# Sheet2.net
KiCad netlist of a schematic drawn in Altium Designer
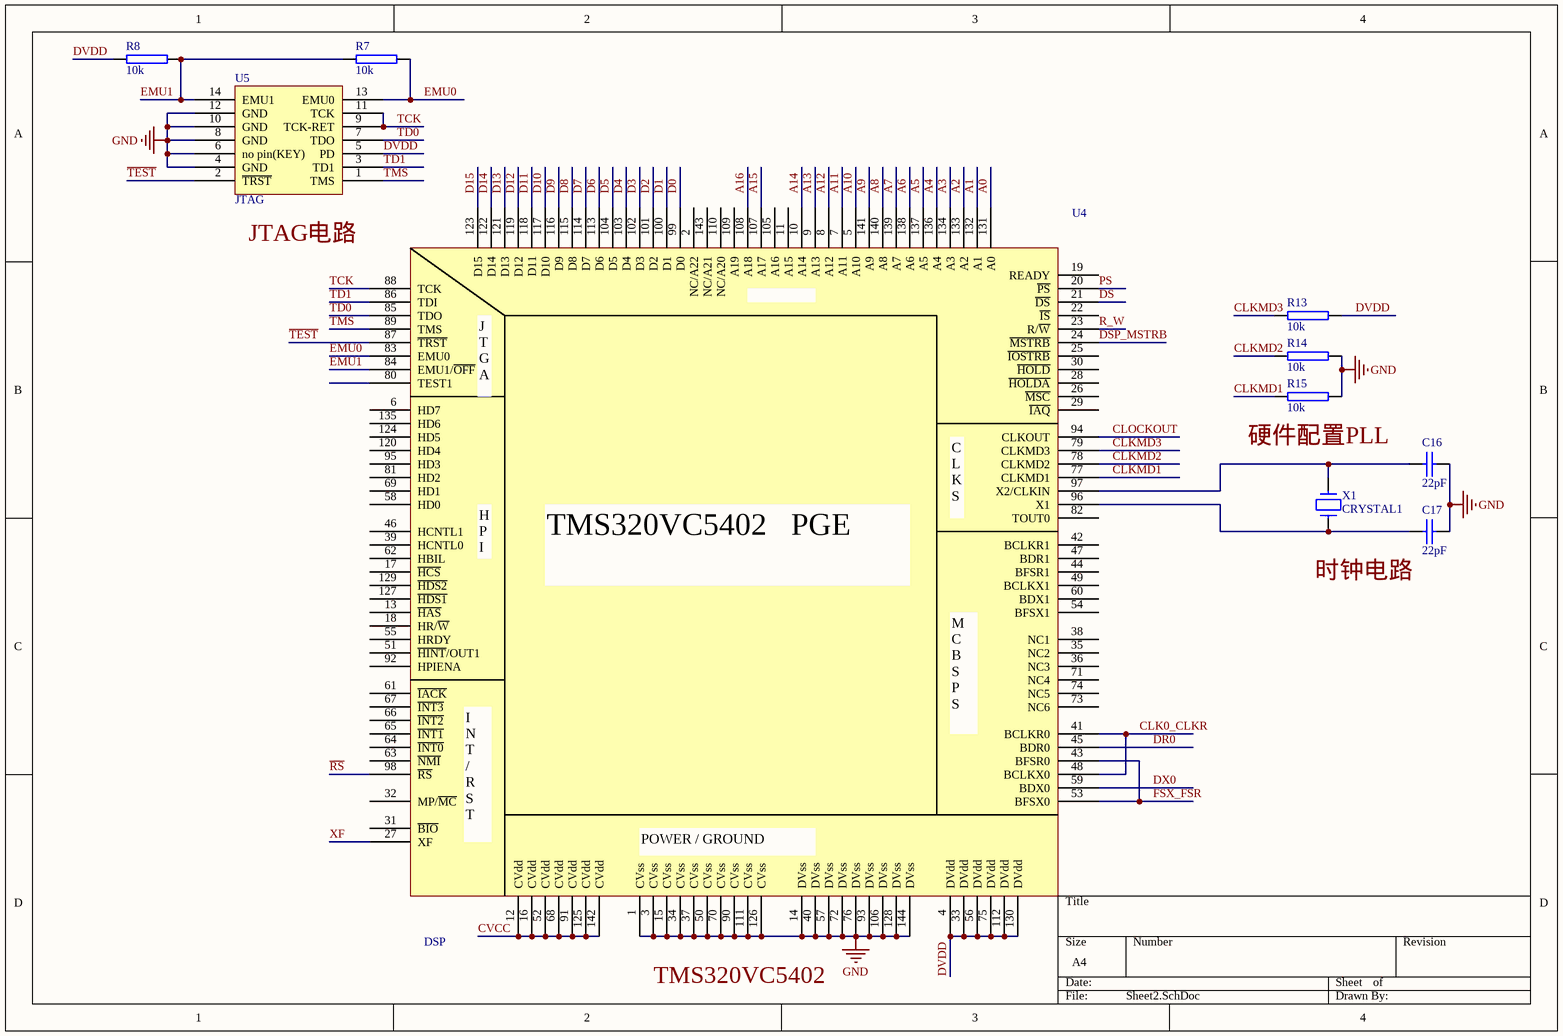
[diagram p0: Sheet2.SchDoc]

(export (version "E")
  (design (tool "Eeschema 10.0.6"))
  (components
    (comp (ref "C16")
      (value "22pF")
      (footprint "C/5/4/2/R2")
      (description "Capacitor")
      (libsource (lib "SCHLIB(2003.4.23)dxp2004") (part "CAP"))
    )
    (comp (ref "C17")
      (value "22pF")
      (footprint "C/5/4/2/R2")
      (description "Capacitor")
      (libsource (lib "SCHLIB(2003.4.23)dxp2004") (part "CAP"))
    )
    (comp (ref "R7") (value "10k") (libsource (lib "wangjin_sch") (part "RES2")))
    (comp (ref "R8") (value "10k") (libsource (lib "wangjin_sch") (part "RES2")))
    (comp (ref "R13") (value "10k") (libsource (lib "wangjin_sch") (part "RES2")))
    (comp (ref "R14") (value "10k") (libsource (lib "wangjin_sch") (part "RES2")))
    (comp (ref "R15") (value "10k") (libsource (lib "wangjin_sch") (part "RES2")))
    (comp (ref "U4") (value "DSP") (libsource (lib "Schlib1") (part "DSP")))
    (comp (ref "U5") (value "JTAG") (libsource (lib "Schlib1") (part "JTAG")))
    (comp (ref "X1")
      (value "CRYSTAL1")
      (footprint "X/2.5/2/6/2.5")
      (description "Crystal")
      (libsource (lib "SCHLIB(2003.4.23)dxp2004") (part "CRYSTAL1"))
    )
  )
  (nets
    (net (code "1") (name "/A0") (class "Default")
      (node (ref "U4") (pin "131") (pinfunction "A0_131") (pintype "passive"))
    )
    (net (code "2") (name "/A1") (class "Default")
      (node (ref "U4") (pin "132") (pinfunction "A1_132") (pintype "passive"))
    )
    (net (code "3") (name "/A2") (class "Default")
      (node (ref "U4") (pin "133") (pinfunction "A2_133") (pintype "passive"))
    )
    (net (code "4") (name "/A3") (class "Default")
      (node (ref "U4") (pin "134") (pinfunction "A3_134") (pintype "passive"))
    )
    (net (code "5") (name "/A4") (class "Default")
      (node (ref "U4") (pin "136") (pinfunction "A4_136") (pintype "passive"))
    )
    (net (code "6") (name "/A5") (class "Default")
      (node (ref "U4") (pin "137") (pinfunction "A5_137") (pintype "passive"))
    )
    (net (code "7") (name "/A6") (class "Default")
      (node (ref "U4") (pin "138") (pinfunction "A6_138") (pintype "passive"))
    )
    (net (code "8") (name "/A7") (class "Default")
      (node (ref "U4") (pin "139") (pinfunction "A7_139") (pintype "passive"))
    )
    (net (code "9") (name "/A8") (class "Default")
      (node (ref "U4") (pin "140") (pinfunction "A8_140") (pintype "passive"))
    )
    (net (code "10") (name "/A9") (class "Default")
      (node (ref "U4") (pin "141") (pinfunction "A9_141") (pintype "passive"))
    )
    (net (code "11") (name "/A10") (class "Default")
      (node (ref "U4") (pin "5") (pinfunction "A10_5") (pintype "passive"))
    )
    (net (code "12") (name "/A11") (class "Default")
      (node (ref "U4") (pin "7") (pinfunction "A11_7") (pintype "passive"))
    )
    (net (code "13") (name "/A12") (class "Default")
      (node (ref "U4") (pin "8") (pinfunction "A12_8") (pintype "passive"))
    )
    (net (code "14") (name "/A13") (class "Default")
      (node (ref "U4") (pin "9") (pinfunction "A13_9") (pintype "passive"))
    )
    (net (code "15") (name "/A14") (class "Default")
      (node (ref "U4") (pin "10") (pinfunction "A14_10") (pintype "passive"))
    )
    (net (code "16") (name "/A15") (class "Default")
      (node (ref "U4") (pin "107") (pinfunction "A17_107") (pintype "passive"))
    )
    (net (code "17") (name "/A16") (class "Default")
      (node (ref "U4") (pin "108") (pinfunction "A18_108") (pintype "passive"))
    )
    (net (code "18") (name "/CLK0_CLKR") (class "Default")
      (node (ref "U4") (pin "41") (pinfunction "BCLKR0_41") (pintype "passive"))
      (node (ref "U4") (pin "48") (pinfunction "BCLKX0_48") (pintype "passive"))
    )
    (net (code "19") (name "/CLKMD1") (class "Default")
      (node (ref "R15") (pin "2") (pinfunction "2_2") (pintype "passive"))
      (node (ref "U4") (pin "77") (pinfunction "CLKMD1_77") (pintype "passive"))
    )
    (net (code "20") (name "/CLKMD2") (class "Default")
      (node (ref "R14") (pin "2") (pinfunction "2_2") (pintype "passive"))
      (node (ref "U4") (pin "78") (pinfunction "CLKMD2_78") (pintype "passive"))
    )
    (net (code "21") (name "/CLKMD3") (class "Default")
      (node (ref "R13") (pin "2") (pinfunction "2_2") (pintype "passive"))
      (node (ref "U4") (pin "79") (pinfunction "CLKMD3_79") (pintype "passive"))
    )
    (net (code "22") (name "/CLOCKOUT") (class "Default")
      (node (ref "U4") (pin "94") (pinfunction "CLKOUT_94") (pintype "passive"))
    )
    (net (code "23") (name "/CVCC") (class "Default")
      (node (ref "U4") (pin "12") (pinfunction "CVdd_12") (pintype "passive"))
      (node (ref "U4") (pin "125") (pinfunction "CVdd_125") (pintype "passive"))
      (node (ref "U4") (pin "142") (pinfunction "CVdd_142") (pintype "passive"))
      (node (ref "U4") (pin "16") (pinfunction "CVdd_16") (pintype "passive"))
      (node (ref "U4") (pin "52") (pinfunction "CVdd_52") (pintype "passive"))
      (node (ref "U4") (pin "68") (pinfunction "CVdd_68") (pintype "passive"))
      (node (ref "U4") (pin "91") (pinfunction "CVdd_91") (pintype "passive"))
    )
    (net (code "24") (name "/D0") (class "Default")
      (node (ref "U4") (pin "99") (pinfunction "D0_99") (pintype "passive"))
    )
    (net (code "25") (name "/D1") (class "Default")
      (node (ref "U4") (pin "100") (pinfunction "D1_100") (pintype "passive"))
    )
    (net (code "26") (name "/D2") (class "Default")
      (node (ref "U4") (pin "101") (pinfunction "D2_101") (pintype "passive"))
    )
    (net (code "27") (name "/D3") (class "Default")
      (node (ref "U4") (pin "102") (pinfunction "D3_102") (pintype "passive"))
    )
    (net (code "28") (name "/D4") (class "Default")
      (node (ref "U4") (pin "103") (pinfunction "D4_103") (pintype "passive"))
    )
    (net (code "29") (name "/D5") (class "Default")
      (node (ref "U4") (pin "104") (pinfunction "D5_104") (pintype "passive"))
    )
    (net (code "30") (name "/D6") (class "Default")
      (node (ref "U4") (pin "113") (pinfunction "D6_113") (pintype "passive"))
    )
    (net (code "31") (name "/D7") (class "Default")
      (node (ref "U4") (pin "114") (pinfunction "D7_114") (pintype "passive"))
    )
    (net (code "32") (name "/D8") (class "Default")
      (node (ref "U4") (pin "115") (pinfunction "D8_115") (pintype "passive"))
    )
    (net (code "33") (name "/D9") (class "Default")
      (node (ref "U4") (pin "116") (pinfunction "D9_116") (pintype "passive"))
    )
    (net (code "34") (name "/D10") (class "Default")
      (node (ref "U4") (pin "117") (pinfunction "D10_117") (pintype "passive"))
    )
    (net (code "35") (name "/D11") (class "Default")
      (node (ref "U4") (pin "118") (pinfunction "D11_118") (pintype "passive"))
    )
    (net (code "36") (name "/D12") (class "Default")
      (node (ref "U4") (pin "119") (pinfunction "D12_119") (pintype "passive"))
    )
    (net (code "37") (name "/D13") (class "Default")
      (node (ref "U4") (pin "121") (pinfunction "D13_121") (pintype "passive"))
    )
    (net (code "38") (name "/D14") (class "Default")
      (node (ref "U4") (pin "122") (pinfunction "D14_122") (pintype "passive"))
    )
    (net (code "39") (name "/D15") (class "Default")
      (node (ref "U4") (pin "123") (pinfunction "D15_123") (pintype "passive"))
    )
    (net (code "40") (name "/DR0") (class "Default")
      (node (ref "U4") (pin "45") (pinfunction "BDR0_45") (pintype "passive"))
    )
    (net (code "41") (name "/DS") (class "Default")
      (node (ref "U4") (pin "21") (pinfunction "~{DS}_21") (pintype "passive"))
    )
    (net (code "42") (name "/DSP_MSTRB") (class "Default")
      (node (ref "U4") (pin "24") (pinfunction "~{MSTRB}_24") (pintype "passive"))
    )
    (net (code "43") (name "/DVDD") (class "Default")
      (node (ref "R13") (pin "1") (pinfunction "1_1") (pintype "passive"))
      (node (ref "R8") (pin "1") (pinfunction "1_1") (pintype "passive"))
      (node (ref "U4") (pin "112") (pinfunction "DVdd_112") (pintype "passive"))
      (node (ref "U4") (pin "130") (pinfunction "DVdd_130") (pintype "passive"))
      (node (ref "U4") (pin "33") (pinfunction "DVdd_33") (pintype "passive"))
      (node (ref "U4") (pin "4") (pinfunction "DVdd_4") (pintype "passive"))
      (node (ref "U4") (pin "56") (pinfunction "DVdd_56") (pintype "passive"))
      (node (ref "U4") (pin "75") (pinfunction "DVdd_75") (pintype "passive"))
      (node (ref "U5") (pin "5") (pinfunction "PD_5") (pintype "passive"))
    )
    (net (code "44") (name "/DX0") (class "Default")
      (node (ref "U4") (pin "59") (pinfunction "BDX0_59") (pintype "passive"))
    )
    (net (code "45") (name "/EMU0") (class "Default")
      (node (ref "R7") (pin "1") (pinfunction "1_1") (pintype "passive"))
      (node (ref "U4") (pin "83") (pinfunction "EMU0_83") (pintype "passive"))
      (node (ref "U5") (pin "13") (pinfunction "EMU0_13") (pintype "passive"))
    )
    (net (code "46") (name "/EMU1") (class "Default")
      (node (ref "R7") (pin "2") (pinfunction "2_2") (pintype "passive"))
      (node (ref "R8") (pin "2") (pinfunction "2_2") (pintype "passive"))
      (node (ref "U4") (pin "84") (pinfunction "EMU1/~{OFF}_84") (pintype "passive"))
      (node (ref "U5") (pin "14") (pinfunction "EMU1_14") (pintype "passive"))
    )
    (net (code "47") (name "/FSX_FSR") (class "Default")
      (node (ref "U4") (pin "43") (pinfunction "BFSR0_43") (pintype "passive"))
      (node (ref "U4") (pin "53") (pinfunction "BFSX0_53") (pintype "passive"))
    )
    (net (code "49") (name "/PS") (class "Default")
      (node (ref "U4") (pin "20") (pinfunction "~{PS}_20") (pintype "passive"))
    )
    (net (code "50") (name "/R_W") (class "Default")
      (node (ref "U4") (pin "23") (pinfunction "R/~{W}_23") (pintype "passive"))
    )
    (net (code "51") (name "/TCK") (class "Default")
      (node (ref "U4") (pin "88") (pinfunction "TCK_88") (pintype "passive"))
      (node (ref "U5") (pin "11") (pinfunction "TCK_11") (pintype "passive"))
      (node (ref "U5") (pin "9") (pinfunction "TCK-RET_9") (pintype "passive"))
    )
    (net (code "52") (name "/TD0") (class "Default")
      (node (ref "U4") (pin "85") (pinfunction "TDO_85") (pintype "passive"))
      (node (ref "U5") (pin "7") (pinfunction "TDO_7") (pintype "passive"))
    )
    (net (code "53") (name "/TD1") (class "Default")
      (node (ref "U4") (pin "86") (pinfunction "TDI_86") (pintype "passive"))
      (node (ref "U5") (pin "3") (pinfunction "TD1_3") (pintype "passive"))
    )
    (net (code "54") (name "/TMS") (class "Default")
      (node (ref "U4") (pin "89") (pinfunction "TMS_89") (pintype "passive"))
      (node (ref "U5") (pin "1") (pinfunction "TMS_1") (pintype "passive"))
    )
    (net (code "56") (name "/XF") (class "Default")
      (node (ref "U4") (pin "27") (pinfunction "XF_27") (pintype "passive"))
    )
    (net (code "57") (name "/~{RS}") (class "Default")
      (node (ref "U4") (pin "98") (pinfunction "~{RS}_98") (pintype "passive"))
    )
    (net (code "58") (name "/~{TEST}") (class "Default")
      (node (ref "U4") (pin "87") (pinfunction "~{TRST}_87") (pintype "passive"))
      (node (ref "U5") (pin "2") (pinfunction "~{TRST}_2") (pintype "passive"))
    )
    (net (code "61") (name "GND") (class "Default")
      (node (ref "C16") (pin "2") (pinfunction "2_2") (pintype "passive"))
      (node (ref "C17") (pin "2") (pinfunction "2_2") (pintype "passive"))
      (node (ref "R14") (pin "1") (pinfunction "1_1") (pintype "passive"))
      (node (ref "R15") (pin "1") (pinfunction "1_1") (pintype "passive"))
      (node (ref "U4") (pin "1") (pinfunction "CVss_1") (pintype "passive"))
      (node (ref "U4") (pin "106") (pinfunction "DVss_106") (pintype "passive"))
      (node (ref "U4") (pin "111") (pinfunction "CVss_111") (pintype "passive"))
      (node (ref "U4") (pin "126") (pinfunction "CVss_126") (pintype "passive"))
      (node (ref "U4") (pin "128") (pinfunction "DVss_128") (pintype "passive"))
      (node (ref "U4") (pin "14") (pinfunction "DVss_14") (pintype "passive"))
      (node (ref "U4") (pin "144") (pinfunction "DVss_144") (pintype "passive"))
      (node (ref "U4") (pin "15") (pinfunction "CVss_15") (pintype "passive"))
      (node (ref "U4") (pin "3") (pinfunction "CVss_3") (pintype "passive"))
      (node (ref "U4") (pin "34") (pinfunction "CVss_34") (pintype "passive"))
      (node (ref "U4") (pin "37") (pinfunction "CVss_37") (pintype "passive"))
      (node (ref "U4") (pin "40") (pinfunction "DVss_40") (pintype "passive"))
      (node (ref "U4") (pin "50") (pinfunction "CVss_50") (pintype "passive"))
      (node (ref "U4") (pin "57") (pinfunction "DVss_57") (pintype "passive"))
      (node (ref "U4") (pin "70") (pinfunction "CVss_70") (pintype "passive"))
      (node (ref "U4") (pin "72") (pinfunction "DVss_72") (pintype "passive"))
      (node (ref "U4") (pin "76") (pinfunction "DVss_76") (pintype "passive"))
      (node (ref "U4") (pin "90") (pinfunction "CVss_90") (pintype "passive"))
      (node (ref "U4") (pin "93") (pinfunction "DVss_93") (pintype "passive"))
      (node (ref "U5") (pin "10") (pinfunction "GND_10") (pintype "passive"))
      (node (ref "U5") (pin "12") (pinfunction "GND_12") (pintype "passive"))
      (node (ref "U5") (pin "4") (pinfunction "GND_4") (pintype "passive"))
      (node (ref "U5") (pin "6") (pinfunction "no_pin(KEY)_6") (pintype "passive"))
      (node (ref "U5") (pin "8") (pinfunction "GND_8") (pintype "passive"))
    )
    (net (code "62") (name "Net-(U4-X1)") (class "Default")
      (node (ref "C17") (pin "1") (pinfunction "1_1") (pintype "passive"))
      (node (ref "U4") (pin "96") (pinfunction "X1_96") (pintype "passive"))
      (node (ref "X1") (pin "2") (pinfunction "2_2") (pintype "passive"))
    )
    (net (code "63") (name "Net-(U4-X2{slash}CLKIN)") (class "Default")
      (node (ref "C16") (pin "1") (pinfunction "1_1") (pintype "passive"))
      (node (ref "U4") (pin "97") (pinfunction "X2/CLKIN_97") (pintype "passive"))
      (node (ref "X1") (pin "1") (pinfunction "1_1") (pintype "passive"))
    )
    (net (code "64") (name "unconnected-(U4-A15-Pad11)") (class "Default")
      (node (ref "U4") (pin "11") (pinfunction "A15_11") (pintype "passive"))
    )
    (net (code "65") (name "unconnected-(U4-A16-Pad105)") (class "Default")
      (node (ref "U4") (pin "105") (pinfunction "A16_105") (pintype "passive"))
    )
    (net (code "66") (name "unconnected-(U4-A19-Pad109)") (class "Default")
      (node (ref "U4") (pin "109") (pinfunction "A19_109") (pintype "passive"))
    )
    (net (code "67") (name "unconnected-(U4-BCLKR1-Pad42)") (class "Default")
      (node (ref "U4") (pin "42") (pinfunction "BCLKR1_42") (pintype "passive"))
    )
    (net (code "68") (name "unconnected-(U4-BCLKX1-Pad49)") (class "Default")
      (node (ref "U4") (pin "49") (pinfunction "BCLKX1_49") (pintype "passive"))
    )
    (net (code "69") (name "unconnected-(U4-BDR1-Pad47)") (class "Default")
      (node (ref "U4") (pin "47") (pinfunction "BDR1_47") (pintype "passive"))
    )
    (net (code "70") (name "unconnected-(U4-BDX1-Pad60)") (class "Default")
      (node (ref "U4") (pin "60") (pinfunction "BDX1_60") (pintype "passive"))
    )
    (net (code "71") (name "unconnected-(U4-BFSR1-Pad44)") (class "Default")
      (node (ref "U4") (pin "44") (pinfunction "BFSR1_44") (pintype "passive"))
    )
    (net (code "72") (name "unconnected-(U4-BFSX1-Pad54)") (class "Default")
      (node (ref "U4") (pin "54") (pinfunction "BFSX1_54") (pintype "passive"))
    )
    (net (code "73") (name "unconnected-(U4-HBIL-Pad62)") (class "Default")
      (node (ref "U4") (pin "62") (pinfunction "HBIL_62") (pintype "passive"))
    )
    (net (code "74") (name "unconnected-(U4-HCNTL0-Pad39)") (class "Default")
      (node (ref "U4") (pin "39") (pinfunction "HCNTL0_39") (pintype "passive"))
    )
    (net (code "75") (name "unconnected-(U4-HCNTL1-Pad46)") (class "Default")
      (node (ref "U4") (pin "46") (pinfunction "HCNTL1_46") (pintype "passive"))
    )
    (net (code "76") (name "unconnected-(U4-HD0-Pad58)") (class "Default")
      (node (ref "U4") (pin "58") (pinfunction "HD0_58") (pintype "passive"))
    )
    (net (code "77") (name "unconnected-(U4-HD1-Pad69)") (class "Default")
      (node (ref "U4") (pin "69") (pinfunction "HD1_69") (pintype "passive"))
    )
    (net (code "78") (name "unconnected-(U4-HD2-Pad81)") (class "Default")
      (node (ref "U4") (pin "81") (pinfunction "HD2_81") (pintype "passive"))
    )
    (net (code "79") (name "unconnected-(U4-HD3-Pad95)") (class "Default")
      (node (ref "U4") (pin "95") (pinfunction "HD3_95") (pintype "passive"))
    )
    (net (code "80") (name "unconnected-(U4-HD4-Pad120)") (class "Default")
      (node (ref "U4") (pin "120") (pinfunction "HD4_120") (pintype "passive"))
    )
    (net (code "81") (name "unconnected-(U4-HD5-Pad124)") (class "Default")
      (node (ref "U4") (pin "124") (pinfunction "HD5_124") (pintype "passive"))
    )
    (net (code "82") (name "unconnected-(U4-HD6-Pad135)") (class "Default")
      (node (ref "U4") (pin "135") (pinfunction "HD6_135") (pintype "passive"))
    )
    (net (code "83") (name "unconnected-(U4-HD7-Pad6)") (class "Default")
      (node (ref "U4") (pin "6") (pinfunction "HD7_6") (pintype "passive"))
    )
    (net (code "84") (name "unconnected-(U4-HPIENA-Pad92)") (class "Default")
      (node (ref "U4") (pin "92") (pinfunction "HPIENA_92") (pintype "passive"))
    )
    (net (code "85") (name "unconnected-(U4-HRDY-Pad55)") (class "Default")
      (node (ref "U4") (pin "55") (pinfunction "HRDY_55") (pintype "passive"))
    )
    (net (code "86") (name "unconnected-(U4-HR{slash}~{W}-Pad18)") (class "Default")
      (node (ref "U4") (pin "18") (pinfunction "HR/~{W}_18") (pintype "passive"))
    )
    (net (code "87") (name "unconnected-(U4-MP{slash}~{MC}-Pad32)") (class "Default")
      (node (ref "U4") (pin "32") (pinfunction "MP/~{MC}_32") (pintype "passive"))
    )
    (net (code "88") (name "unconnected-(U4-NC1-Pad38)") (class "Default")
      (node (ref "U4") (pin "38") (pinfunction "NC1_38") (pintype "passive"))
    )
    (net (code "89") (name "unconnected-(U4-NC2-Pad35)") (class "Default")
      (node (ref "U4") (pin "35") (pinfunction "NC2_35") (pintype "passive"))
    )
    (net (code "90") (name "unconnected-(U4-NC3-Pad36)") (class "Default")
      (node (ref "U4") (pin "36") (pinfunction "NC3_36") (pintype "passive"))
    )
    (net (code "91") (name "unconnected-(U4-NC4-Pad71)") (class "Default")
      (node (ref "U4") (pin "71") (pinfunction "NC4_71") (pintype "passive"))
    )
    (net (code "92") (name "unconnected-(U4-NC5-Pad74)") (class "Default")
      (node (ref "U4") (pin "74") (pinfunction "NC5_74") (pintype "passive"))
    )
    (net (code "93") (name "unconnected-(U4-NC6-Pad73)") (class "Default")
      (node (ref "U4") (pin "73") (pinfunction "NC6_73") (pintype "passive"))
    )
    (net (code "94") (name "unconnected-(U4-NC{slash}A20-Pad110)") (class "Default")
      (node (ref "U4") (pin "110") (pinfunction "NC/A20_110") (pintype "passive"))
    )
    (net (code "95") (name "unconnected-(U4-NC{slash}A21-Pad143)") (class "Default")
      (node (ref "U4") (pin "143") (pinfunction "NC/A21_143") (pintype "passive"))
    )
    (net (code "96") (name "unconnected-(U4-NC{slash}A22-Pad2)") (class "Default")
      (node (ref "U4") (pin "2") (pinfunction "NC/A22_2") (pintype "passive"))
    )
    (net (code "97") (name "unconnected-(U4-READY-Pad19)") (class "Default")
      (node (ref "U4") (pin "19") (pinfunction "READY_19") (pintype "passive"))
    )
    (net (code "98") (name "unconnected-(U4-TEST1-Pad80)") (class "Default")
      (node (ref "U4") (pin "80") (pinfunction "TEST1_80") (pintype "passive"))
    )
    (net (code "99") (name "unconnected-(U4-TOUT0-Pad82)") (class "Default")
      (node (ref "U4") (pin "82") (pinfunction "TOUT0_82") (pintype "passive"))
    )
    (net (code "100") (name "unconnected-(U4-~{BIO}-Pad31)") (class "Default")
      (node (ref "U4") (pin "31") (pinfunction "~{BIO}_31") (pintype "passive"))
    )
    (net (code "101") (name "unconnected-(U4-~{HAS}-Pad13)") (class "Default")
      (node (ref "U4") (pin "13") (pinfunction "~{HAS}_13") (pintype "passive"))
    )
    (net (code "102") (name "unconnected-(U4-~{HCS}-Pad17)") (class "Default")
      (node (ref "U4") (pin "17") (pinfunction "~{HCS}_17") (pintype "passive"))
    )
    (net (code "103") (name "unconnected-(U4-~{HDS1}-Pad127)") (class "Default")
      (node (ref "U4") (pin "127") (pinfunction "~{HDS1}_127") (pintype "passive"))
    )
    (net (code "104") (name "unconnected-(U4-~{HDS2}-Pad129)") (class "Default")
      (node (ref "U4") (pin "129") (pinfunction "~{HDS2}_129") (pintype "passive"))
    )
    (net (code "105") (name "unconnected-(U4-~{HINT}{slash}OUT1-Pad51)") (class "Default")
      (node (ref "U4") (pin "51") (pinfunction "~{HINT}/OUT1_51") (pintype "passive"))
    )
    (net (code "106") (name "unconnected-(U4-~{HOLDA}-Pad28)") (class "Default")
      (node (ref "U4") (pin "28") (pinfunction "~{HOLDA}_28") (pintype "passive"))
    )
    (net (code "107") (name "unconnected-(U4-~{HOLD}-Pad30)") (class "Default")
      (node (ref "U4") (pin "30") (pinfunction "~{HOLD}_30") (pintype "passive"))
    )
    (net (code "108") (name "unconnected-(U4-~{IACK}-Pad61)") (class "Default")
      (node (ref "U4") (pin "61") (pinfunction "~{IACK}_61") (pintype "passive"))
    )
    (net (code "109") (name "unconnected-(U4-~{IAQ}-Pad29)") (class "Default")
      (node (ref "U4") (pin "29") (pinfunction "~{IAQ}_29") (pintype "passive"))
    )
    (net (code "110") (name "unconnected-(U4-~{INT0}-Pad64)") (class "Default")
      (node (ref "U4") (pin "64") (pinfunction "~{INT0}_64") (pintype "passive"))
    )
    (net (code "111") (name "unconnected-(U4-~{INT1}-Pad65)") (class "Default")
      (node (ref "U4") (pin "65") (pinfunction "~{INT1}_65") (pintype "passive"))
    )
    (net (code "112") (name "unconnected-(U4-~{INT2}-Pad66)") (class "Default")
      (node (ref "U4") (pin "66") (pinfunction "~{INT2}_66") (pintype "passive"))
    )
    (net (code "113") (name "unconnected-(U4-~{INT3}-Pad67)") (class "Default")
      (node (ref "U4") (pin "67") (pinfunction "~{INT3}_67") (pintype "passive"))
    )
    (net (code "114") (name "unconnected-(U4-~{IOSTRB}-Pad25)") (class "Default")
      (node (ref "U4") (pin "25") (pinfunction "~{IOSTRB}_25") (pintype "passive"))
    )
    (net (code "115") (name "unconnected-(U4-~{IS}-Pad22)") (class "Default")
      (node (ref "U4") (pin "22") (pinfunction "~{IS}_22") (pintype "passive"))
    )
    (net (code "116") (name "unconnected-(U4-~{MSC}-Pad26)") (class "Default")
      (node (ref "U4") (pin "26") (pinfunction "~{MSC}_26") (pintype "passive"))
    )
    (net (code "117") (name "unconnected-(U4-~{NMI}-Pad63)") (class "Default")
      (node (ref "U4") (pin "63") (pinfunction "~{NMI}_63") (pintype "passive"))
    )
  )
)
